# TerraceClimate.net
KiCad netlist of a schematic drawn in EasyEDA
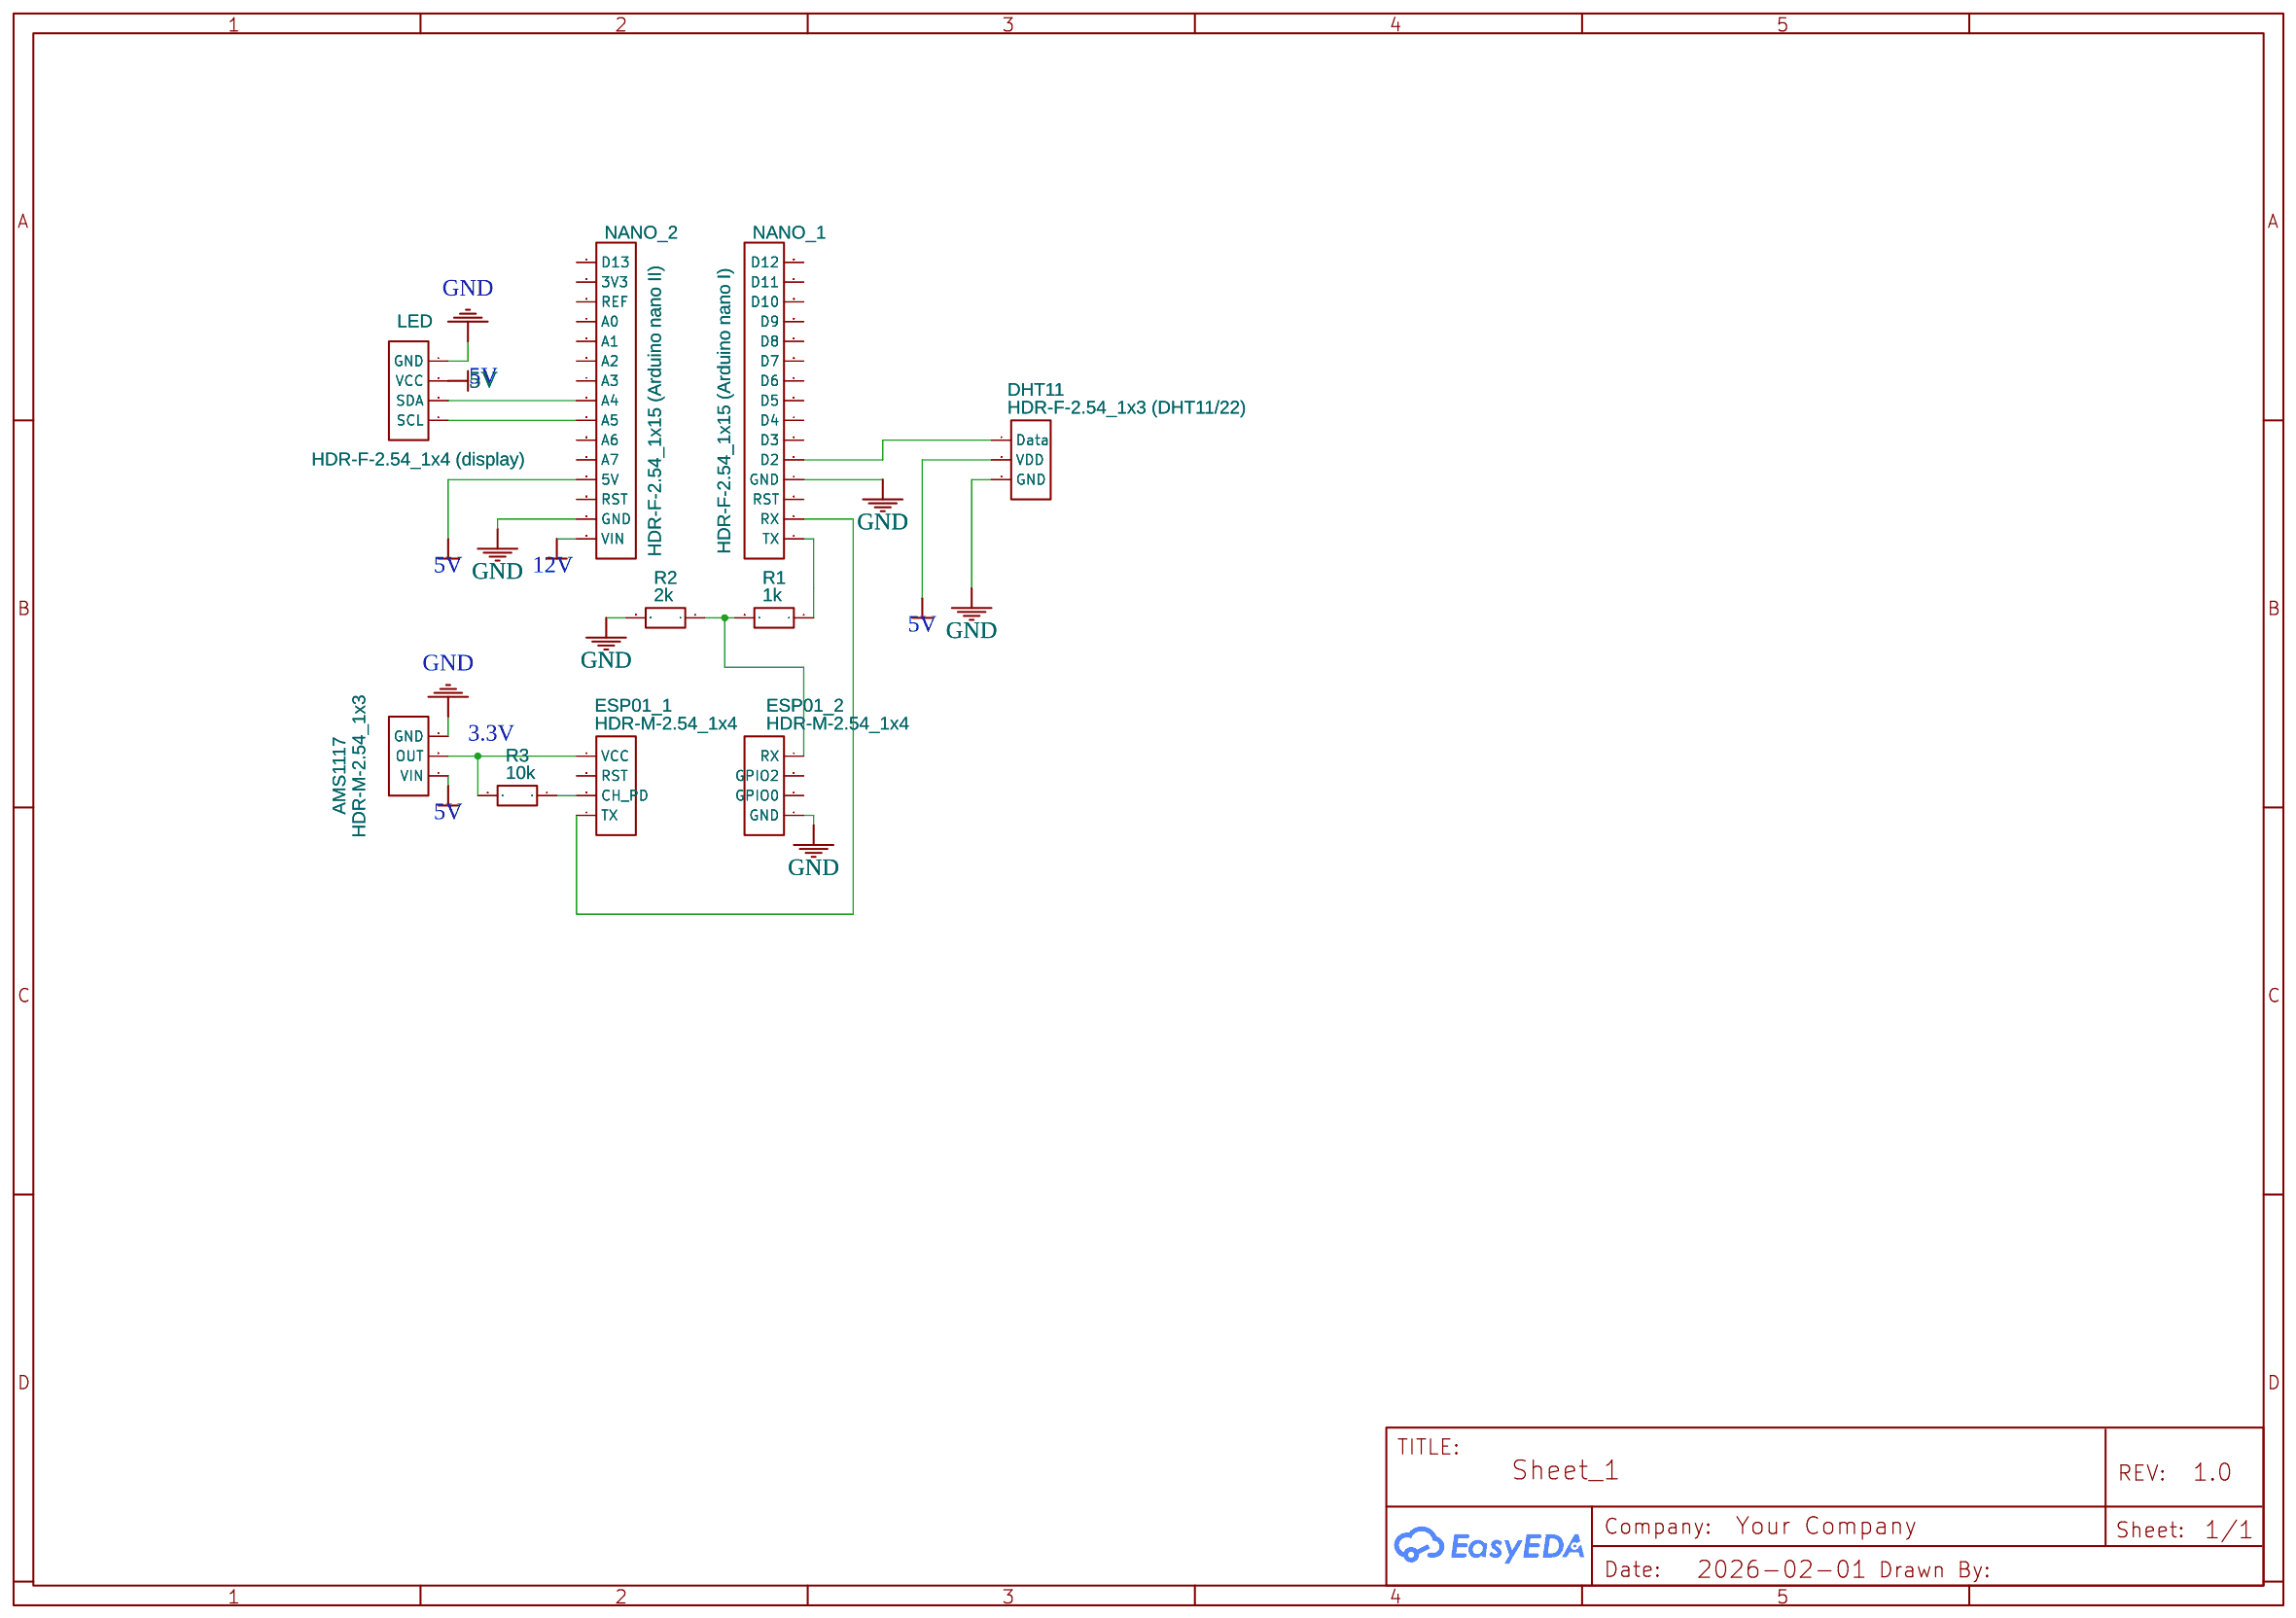
[diagram p0: schematic sheet]

(export (version "E")
  (design (tool "Eeschema 10.0.6"))
  (components
    (comp (ref "AMS1117") (value "HDR-M-2.54_1x3") (libsource (lib "") (part "HDR-M-2.54_1x3")))
    (comp (ref "DHT11") (value "HDR-F-2.54_1x3 (DHT11/22)") (libsource (lib "") (part "HDR-F-2.54_1x3")))
    (comp (ref "ESP01_1") (value "HDR-M-2.54_1x4") (libsource (lib "") (part "HDR-M-2.54_1x4")))
    (comp (ref "ESP01_2") (value "HDR-M-2.54_1x4") (libsource (lib "") (part "HDR-M-2.54_1x4_1")))
    (comp (ref "LED") (value "HDR-F-2.54_1x4 (display)") (libsource (lib "") (part "HDR-F-2.54_1x4")))
    (comp (ref "NANO_1")
      (value "HDR-F-2.54_1x15 (Arduino nano I)")
      (libsource (lib "") (part "HDR-F-2.54_1x15_1"))
    )
    (comp (ref "NANO_2")
      (value "HDR-F-2.54_1x15 (Arduino nano II)")
      (libsource (lib "") (part "HDR-F-2.54_1x15"))
    )
    (comp (ref "R1") (value "1k") (libsource (lib "") (part "R_0603_EU")))
    (comp (ref "R2") (value "2k") (libsource (lib "") (part "R_0603_EU")))
    (comp (ref "R3") (value "10k") (libsource (lib "") (part "R_0603_EU")))
  )
  (nets
    (net (code "1") (name "5V") (class "Default")
      (node (ref "AMS1117") (pin "1") (pinfunction "VIN_1") (pintype "input"))
      (node (ref "DHT11") (pin "2") (pinfunction "VDD_2") (pintype "input"))
      (node (ref "LED") (pin "3") (pinfunction "VCC_3") (pintype "unspecified"))
      (node (ref "NANO_2") (pin "12") (pinfunction "5V_12") (pintype "unspecified"))
    )
    (net (code "2") (name "12V") (class "Default")
      (node (ref "NANO_2") (pin "15") (pinfunction "VIN_15") (pintype "unspecified"))
    )
    (net (code "3") (name "GND") (class "Default")
      (node (ref "AMS1117") (pin "3") (pinfunction "GND_3") (pintype "input"))
      (node (ref "DHT11") (pin "3") (pinfunction "GND_3") (pintype "input"))
      (node (ref "ESP01_2") (pin "1") (pinfunction "GND_1") (pintype "unspecified"))
      (node (ref "LED") (pin "4") (pinfunction "GND_4") (pintype "unspecified"))
      (node (ref "NANO_1") (pin "4") (pinfunction "GND_4") (pintype "unspecified"))
      (node (ref "NANO_2") (pin "14") (pinfunction "GND_14") (pintype "unspecified"))
      (node (ref "R2") (pin "2") (pinfunction "2_2") (pintype "unspecified"))
    )
    (net (code "4") (name "Net-(AMS1117-OUT)") (class "Default")
      (node (ref "AMS1117") (pin "2") (pinfunction "OUT_2") (pintype "input"))
      (node (ref "ESP01_1") (pin "1") (pinfunction "VCC_1") (pintype "unspecified"))
      (node (ref "R3") (pin "2") (pinfunction "2_2") (pintype "unspecified"))
    )
    (net (code "5") (name "Net-(DHT11-Data)") (class "Default")
      (node (ref "DHT11") (pin "1") (pinfunction "Data_1") (pintype "input"))
      (node (ref "NANO_1") (pin "5") (pinfunction "D2_5") (pintype "unspecified"))
    )
    (net (code "6") (name "Net-(ESP01_1-CH_PD)") (class "Default")
      (node (ref "ESP01_1") (pin "3") (pinfunction "CH_PD_3") (pintype "unspecified"))
      (node (ref "R3") (pin "1") (pinfunction "1_1") (pintype "unspecified"))
    )
    (net (code "7") (name "Net-(ESP01_1-TX)") (class "Default")
      (node (ref "ESP01_1") (pin "4") (pinfunction "TX_4") (pintype "unspecified"))
      (node (ref "NANO_1") (pin "2") (pinfunction "RX_2") (pintype "unspecified"))
    )
    (net (code "8") (name "Net-(ESP01_2-RX)") (class "Default")
      (node (ref "ESP01_2") (pin "4") (pinfunction "RX_4") (pintype "unspecified"))
      (node (ref "R1") (pin "2") (pinfunction "2_2") (pintype "unspecified"))
      (node (ref "R2") (pin "1") (pinfunction "1_1") (pintype "unspecified"))
    )
    (net (code "9") (name "Net-(LED-SCL)") (class "Default")
      (node (ref "LED") (pin "1") (pinfunction "SCL_1") (pintype "unspecified"))
      (node (ref "NANO_2") (pin "9") (pinfunction "A5_9") (pintype "unspecified"))
    )
    (net (code "10") (name "Net-(LED-SDA)") (class "Default")
      (node (ref "LED") (pin "2") (pinfunction "SDA_2") (pintype "unspecified"))
      (node (ref "NANO_2") (pin "8") (pinfunction "A4_8") (pintype "unspecified"))
    )
    (net (code "11") (name "Net-(NANO_1-TX)") (class "Default")
      (node (ref "NANO_1") (pin "1") (pinfunction "TX_1") (pintype "unspecified"))
      (node (ref "R1") (pin "1") (pinfunction "1_1") (pintype "unspecified"))
    )
    (net (code "12") (name "unconnected-(ESP01_1-RST-Pad2)") (class "Default")
      (node (ref "ESP01_1") (pin "2") (pinfunction "RST_2") (pintype "unspecified"))
    )
    (net (code "13") (name "unconnected-(ESP01_2-GPIO0-Pad2)") (class "Default")
      (node (ref "ESP01_2") (pin "2") (pinfunction "GPIO0_2") (pintype "unspecified"))
    )
    (net (code "14") (name "unconnected-(ESP01_2-GPIO2-Pad3)") (class "Default")
      (node (ref "ESP01_2") (pin "3") (pinfunction "GPIO2_3") (pintype "unspecified"))
    )
    (net (code "15") (name "unconnected-(NANO_1-D3-Pad6)") (class "Default")
      (node (ref "NANO_1") (pin "6") (pinfunction "D3_6") (pintype "unspecified"))
    )
    (net (code "16") (name "unconnected-(NANO_1-D4-Pad7)") (class "Default")
      (node (ref "NANO_1") (pin "7") (pinfunction "D4_7") (pintype "unspecified"))
    )
    (net (code "17") (name "unconnected-(NANO_1-D5-Pad8)") (class "Default")
      (node (ref "NANO_1") (pin "8") (pinfunction "D5_8") (pintype "unspecified"))
    )
    (net (code "18") (name "unconnected-(NANO_1-D6-Pad9)") (class "Default")
      (node (ref "NANO_1") (pin "9") (pinfunction "D6_9") (pintype "unspecified"))
    )
    (net (code "19") (name "unconnected-(NANO_1-D7-Pad10)") (class "Default")
      (node (ref "NANO_1") (pin "10") (pinfunction "D7_10") (pintype "unspecified"))
    )
    (net (code "20") (name "unconnected-(NANO_1-D8-Pad11)") (class "Default")
      (node (ref "NANO_1") (pin "11") (pinfunction "D8_11") (pintype "unspecified"))
    )
    (net (code "21") (name "unconnected-(NANO_1-D9-Pad12)") (class "Default")
      (node (ref "NANO_1") (pin "12") (pinfunction "D9_12") (pintype "unspecified"))
    )
    (net (code "22") (name "unconnected-(NANO_1-D10-Pad13)") (class "Default")
      (node (ref "NANO_1") (pin "13") (pinfunction "D10_13") (pintype "unspecified"))
    )
    (net (code "23") (name "unconnected-(NANO_1-D11-Pad14)") (class "Default")
      (node (ref "NANO_1") (pin "14") (pinfunction "D11_14") (pintype "unspecified"))
    )
    (net (code "24") (name "unconnected-(NANO_1-D12-Pad15)") (class "Default")
      (node (ref "NANO_1") (pin "15") (pinfunction "D12_15") (pintype "unspecified"))
    )
    (net (code "25") (name "unconnected-(NANO_1-RST-Pad3)") (class "Default")
      (node (ref "NANO_1") (pin "3") (pinfunction "RST_3") (pintype "unspecified"))
    )
    (net (code "26") (name "unconnected-(NANO_2-3V3-Pad2)") (class "Default")
      (node (ref "NANO_2") (pin "2") (pinfunction "3V3_2") (pintype "unspecified"))
    )
    (net (code "27") (name "unconnected-(NANO_2-A0-Pad4)") (class "Default")
      (node (ref "NANO_2") (pin "4") (pinfunction "A0_4") (pintype "unspecified"))
    )
    (net (code "28") (name "unconnected-(NANO_2-A1-Pad5)") (class "Default")
      (node (ref "NANO_2") (pin "5") (pinfunction "A1_5") (pintype "unspecified"))
    )
    (net (code "29") (name "unconnected-(NANO_2-A2-Pad6)") (class "Default")
      (node (ref "NANO_2") (pin "6") (pinfunction "A2_6") (pintype "unspecified"))
    )
    (net (code "30") (name "unconnected-(NANO_2-A3-Pad7)") (class "Default")
      (node (ref "NANO_2") (pin "7") (pinfunction "A3_7") (pintype "unspecified"))
    )
    (net (code "31") (name "unconnected-(NANO_2-A6-Pad10)") (class "Default")
      (node (ref "NANO_2") (pin "10") (pinfunction "A6_10") (pintype "unspecified"))
    )
    (net (code "32") (name "unconnected-(NANO_2-A7-Pad11)") (class "Default")
      (node (ref "NANO_2") (pin "11") (pinfunction "A7_11") (pintype "unspecified"))
    )
    (net (code "33") (name "unconnected-(NANO_2-D13-Pad1)") (class "Default")
      (node (ref "NANO_2") (pin "1") (pinfunction "D13_1") (pintype "unspecified"))
    )
    (net (code "34") (name "unconnected-(NANO_2-REF-Pad3)") (class "Default")
      (node (ref "NANO_2") (pin "3") (pinfunction "REF_3") (pintype "unspecified"))
    )
    (net (code "35") (name "unconnected-(NANO_2-RST-Pad13)") (class "Default")
      (node (ref "NANO_2") (pin "13") (pinfunction "RST_13") (pintype "unspecified"))
    )
  )
)
